# DRV10975_3-ph_Sensorless_BLDC_Motor_Driv.net
KiCad netlist of a schematic drawn in Altium Designer
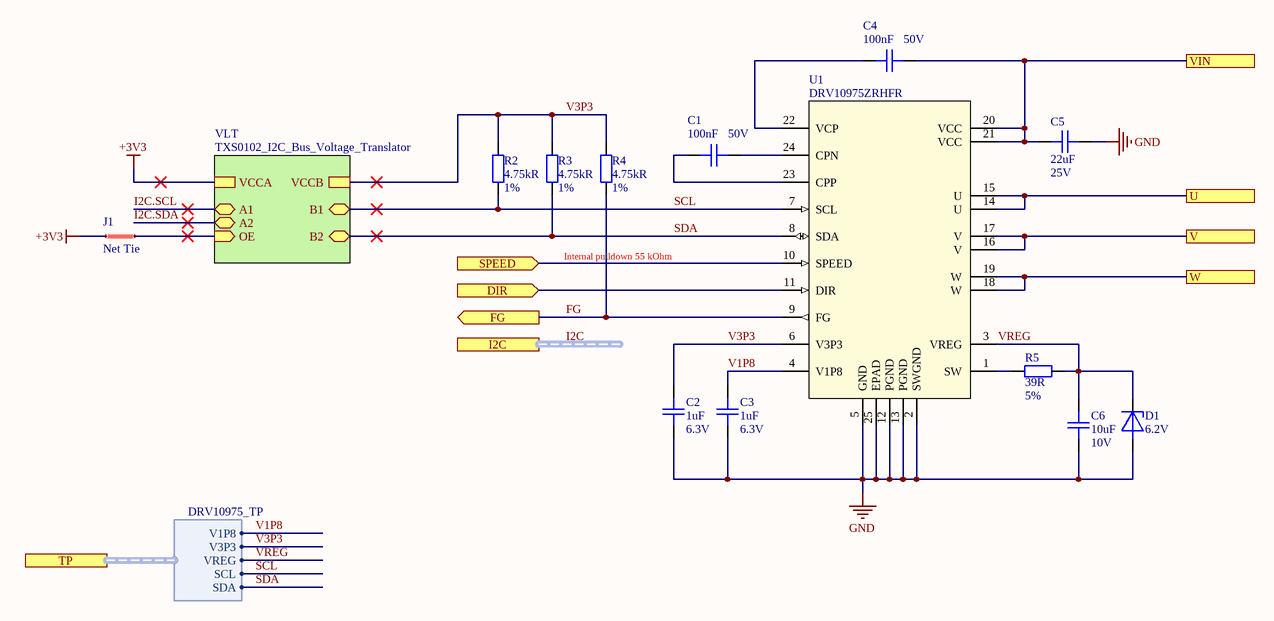
[diagram p0: DRV10975 3-ph Sensorless BLDC Motor Driver.SchDoc]

(export (version "E")
  (design (tool "Eeschema 10.0.6"))
  (components
    (comp (ref "C1")
      (value "CAP CER 0.1UF 50V X7R 0402")
      (footprint "C0402")
      (description "0.1µF ±10% 50V Ceramic Capacitor X7R 0402 (1005 Metric)")
      (fields
        (field (name "MANUFACTURER") "TDK")
        (field (name "MANUFACTURER PART NUMBER") "CGA2B3X7R1H104K050BB")
        (field (name "CAPACITANCE") "100nF")
        (field (name "VOLTAGE") "50V")
      )
      (libsource (lib "capacitors_smd") (part "CAP CER 0.1UF 50V X7R 0402"))
    )
    (comp (ref "C2")
      (value "CAP CER 1UF 6.3V X5R 0402")
      (footprint "C0402")
      (description "1µF ±10% 6.3V Ceramic Capacitor X5R 0402 (1005 Metric)")
      (fields
        (field (name "MANUFACTURER") "Yageo")
        (field (name "MANUFACTURER PART NUMBER") "CC0402KRX5R5BB105")
        (field (name "CAPACITANCE") "1uF")
        (field (name "VOLTAGE RATING") "6.3V")
      )
      (libsource (lib "capacitors_smd") (part "CAP CER 1UF 6.3V X5R 0402"))
    )
    (comp (ref "C3")
      (value "CAP CER 1UF 6.3V X5R 0402")
      (footprint "C0402")
      (description "1µF ±10% 6.3V Ceramic Capacitor X5R 0402 (1005 Metric)")
      (fields
        (field (name "MANUFACTURER") "Yageo")
        (field (name "MANUFACTURER PART NUMBER") "CC0402KRX5R5BB105")
        (field (name "CAPACITANCE") "1uF")
        (field (name "VOLTAGE RATING") "6.3V")
      )
      (libsource (lib "capacitors_smd") (part "CAP CER 1UF 6.3V X5R 0402"))
    )
    (comp (ref "C4")
      (value "CAP CER 0.1UF 50V X7R 0402")
      (footprint "C0402")
      (description "0.1µF ±10% 50V Ceramic Capacitor X7R 0402 (1005 Metric)")
      (fields
        (field (name "MANUFACTURER") "TDK")
        (field (name "MANUFACTURER PART NUMBER") "CGA2B3X7R1H104K050BB")
        (field (name "CAPACITANCE") "100nF")
        (field (name "VOLTAGE") "50V")
      )
      (libsource (lib "capacitors_smd") (part "CAP CER 0.1UF 50V X7R 0402"))
    )
    (comp (ref "C5")
      (value "CAP CER 22UF 25V X5R 0805")
      (footprint "C0805")
      (description "22µF ±20% 25V Ceramic Capacitor X5R 0805 (2012 Metric)")
      (fields
        (field (name "MANUFACTURER") "Yageo")
        (field (name "MANUFACTURER PART NUMBER") "CC0805MKX5R8BB226")
        (field (name "CAPACITANCE") "22uF")
        (field (name "VOLTAGE RATING") "25V")
      )
      (libsource (lib "capacitors_smd") (part "CAP CER 22UF 25V X5R 0805"))
    )
    (comp (ref "C6")
      (value "CAP CER 10uF X7R 10% 0805")
      (footprint "C0805")
      (description "Capacitor,10uF,10V,X7R,10%,0805,Murata")
      (fields
        (field (name "MANUFACTURER") "Murata")
        (field (name "MANUFACTURER PART NUMBER") "GRM21BR71A106KA73L")
        (field (name "CAPACITANCE") "10uF")
        (field (name "VOLTAGE RATING") "10V")
      )
      (libsource (lib "capacitors_smd") (part "CAP CER 10uF X7R 10% 0805"))
    )
    (comp (ref "D1")
      (value "Zener Diode 6.2V 2.5W ±5% Surface Mount SOD-123FL")
      (footprint "SOD-123FL")
      (fields
        (field (name "MANUFACTURER") "ON Semiconductor")
        (field (name "MANUFACTURER PART NUMBER") "1SMF5920BT1G")
        (field (name "TOLERANCE") "5%")
        (field (name "ZENER VOLTAGE") "6.2V")
      )
      (libsource (lib "diodes_zener") (part "DIODE ZENER 6.2V 2.5W SOD123FL"))
    )
    (comp (ref "J1")
      (value "Net Tie")
      (footprint "Net Tie 6x30mil")
      (libsource (lib "BLDC_Motor_Driver") (part "Net Tie Line"))
    )
    (comp (ref "R2")
      (value "DNP*")
      (footprint "R0402")
      (description "4.75 kOhms ±1% 0.063W, 1/16W Chip Resistor 0402 (1005 Metric) Moisture Resistant Thick Film")
      (fields
        (field (name "MANUFACTURER") "Yageo")
        (field (name "MANUFACTURER PART NUMBER") "RC0402FR-074K75P")
        (field (name "RESISTANCE") "4.75kR")
        (field (name "TOLERANCE") "1%")
      )
      (libsource (lib "resistors_smd") (part "RES SMD 4.75K OHM 1% 1/16W 0402"))
    )
    (comp (ref "R3")
      (value "DNP*")
      (footprint "R0402")
      (description "4.75 kOhms ±1% 0.063W, 1/16W Chip Resistor 0402 (1005 Metric) Moisture Resistant Thick Film")
      (fields
        (field (name "MANUFACTURER") "Yageo")
        (field (name "MANUFACTURER PART NUMBER") "RC0402FR-074K75P")
        (field (name "RESISTANCE") "4.75kR")
        (field (name "TOLERANCE") "1%")
      )
      (libsource (lib "resistors_smd") (part "RES SMD 4.75K OHM 1% 1/16W 0402"))
    )
    (comp (ref "R4")
      (value "RES SMD 4.75K OHM 1% 1/16W 0402")
      (footprint "R0402")
      (description "4.75 kOhms ±1% 0.063W, 1/16W Chip Resistor 0402 (1005 Metric) Moisture Resistant Thick Film")
      (fields
        (field (name "MANUFACTURER") "Yageo")
        (field (name "MANUFACTURER PART NUMBER") "RC0402FR-074K75P")
        (field (name "RESISTANCE") "4.75kR")
        (field (name "TOLERANCE") "1%")
      )
      (libsource (lib "resistors_smd") (part "RES SMD 4.75K OHM 1% 1/16W 0402"))
    )
    (comp (ref "R5")
      (value "RES SMD 39 OHM 1% 1/4W 1206")
      (footprint "R1206")
      (description "39 Ohms ±5% 0.25W, 1/4W Chip Resistor 1206 (3216 Metric) Moisture Resistant Thick Film")
      (fields
        (field (name "MANUFACTURER") "Yageo")
        (field (name "MANUFACTURER PART NUMBER") "RC1206JR-0739RL")
        (field (name "RESISTANCE") "39R")
        (field (name "TOLERANCE") "5%")
      )
      (libsource (lib "resistors_smd") (part "RES SMD 39 OHM 1% 1/4W 1206"))
    )
    (comp (ref "U1")
      (value "DRV10975ZRHFR")
      (footprint "RHF24_2P65X3P65")
      (description "Multiphase Motor Driver Power MOSFET Analog, I²C, PWM 24-VQFN (5x4)")
      (fields (field (name "MANUFACTURER") "Texas Instruments"))
      (libsource (lib "BLDC_Moto_Driver") (part "IC DRV10975Z BLDC MOTOR DRIVER VQFN-24"))
    )
  )
  (nets
    (net (code "3") (name "+3V3") (class "Default") (node (ref "J1") (pin "1") (pintype "passive")))
    (net (code "4") (name "/DIR") (class "Default")
      (node (ref "U1") (pin "11") (pinfunction "DIR_11") (pintype "input"))
    )
    (net (code "5") (name "/FG") (class "Default")
      (node (ref "R4") (pin "2") (pinfunction "2_2") (pintype "passive"))
      (node (ref "U1") (pin "9") (pinfunction "FG_9") (pintype "output"))
    )
    (net (code "8") (name "/OE") (class "Default") (node (ref "J1") (pin "2") (pintype "passive")))
    (net (code "9") (name "/SCL") (class "Default")
      (node (ref "R2") (pin "2") (pinfunction "2_2") (pintype "passive"))
      (node (ref "U1") (pin "7") (pinfunction "SCL_7") (pintype "input"))
    )
    (net (code "10") (name "/SDA") (class "Default")
      (node (ref "R3") (pin "2") (pinfunction "2_2") (pintype "passive"))
      (node (ref "U1") (pin "8") (pinfunction "SDA_8") (pintype "bidirectional"))
    )
    (net (code "11") (name "/SPEED") (class "Default")
      (node (ref "U1") (pin "10") (pinfunction "SPEED_10") (pintype "input"))
    )
    (net (code "12") (name "/U") (class "Default")
      (node (ref "U1") (pin "14") (pinfunction "U_14") (pintype "power_in"))
      (node (ref "U1") (pin "15") (pinfunction "U_15") (pintype "power_in"))
    )
    (net (code "13") (name "/V") (class "Default")
      (node (ref "U1") (pin "16") (pinfunction "V_16") (pintype "power_in"))
      (node (ref "U1") (pin "17") (pinfunction "V_17") (pintype "power_in"))
    )
    (net (code "14") (name "/V1P8") (class "Default")
      (node (ref "C3") (pin "2") (pinfunction "2_2") (pintype "passive"))
      (node (ref "U1") (pin "4") (pinfunction "V1P8_4") (pintype "power_in"))
    )
    (net (code "15") (name "/V3P3") (class "Default")
      (node (ref "C2") (pin "2") (pinfunction "2_2") (pintype "passive"))
      (node (ref "R2") (pin "1") (pinfunction "1_1") (pintype "passive"))
      (node (ref "R3") (pin "1") (pinfunction "1_1") (pintype "passive"))
      (node (ref "R4") (pin "1") (pinfunction "1_1") (pintype "passive"))
      (node (ref "U1") (pin "6") (pinfunction "V3P3_6") (pintype "power_in"))
    )
    (net (code "16") (name "/VIN") (class "Default")
      (node (ref "C4") (pin "2") (pinfunction "2_2") (pintype "passive"))
      (node (ref "C5") (pin "1") (pinfunction "1_1") (pintype "passive"))
      (node (ref "U1") (pin "20") (pinfunction "VCC_20") (pintype "power_in"))
      (node (ref "U1") (pin "21") (pinfunction "VCC_21") (pintype "power_in"))
    )
    (net (code "17") (name "/VREG") (class "Default")
      (node (ref "C6") (pin "1") (pinfunction "1_1") (pintype "passive"))
      (node (ref "D1") (pin "1") (pinfunction "K_1") (pintype "passive"))
      (node (ref "R5") (pin "2") (pinfunction "2_2") (pintype "passive"))
      (node (ref "U1") (pin "3") (pinfunction "VREG_3") (pintype "power_in"))
    )
    (net (code "18") (name "/W") (class "Default")
      (node (ref "U1") (pin "18") (pinfunction "W_18") (pintype "power_in"))
      (node (ref "U1") (pin "19") (pinfunction "W_19") (pintype "power_in"))
    )
    (net (code "21") (name "GND") (class "Default")
      (node (ref "C2") (pin "1") (pinfunction "1_1") (pintype "passive"))
      (node (ref "C3") (pin "1") (pinfunction "1_1") (pintype "passive"))
      (node (ref "C5") (pin "2") (pinfunction "2_2") (pintype "passive"))
      (node (ref "C6") (pin "2") (pinfunction "2_2") (pintype "passive"))
      (node (ref "D1") (pin "2") (pinfunction "A_2") (pintype "passive"))
      (node (ref "U1") (pin "12") (pinfunction "PGND_12") (pintype "power_in"))
      (node (ref "U1") (pin "13") (pinfunction "PGND_13") (pintype "power_in"))
      (node (ref "U1") (pin "2") (pinfunction "SWGND_2") (pintype "power_in"))
      (node (ref "U1") (pin "25") (pinfunction "EPAD_25") (pintype "power_in"))
      (node (ref "U1") (pin "5") (pinfunction "GND_5") (pintype "power_in"))
    )
    (net (code "22") (name "Net-(U1-CPN)") (class "Default")
      (node (ref "C1") (pin "2") (pinfunction "2_2") (pintype "passive"))
      (node (ref "U1") (pin "24") (pinfunction "CPN_24") (pintype "power_in"))
    )
    (net (code "23") (name "Net-(U1-CPP)") (class "Default")
      (node (ref "C1") (pin "1") (pinfunction "1_1") (pintype "passive"))
      (node (ref "U1") (pin "23") (pinfunction "CPP_23") (pintype "power_in"))
    )
    (net (code "24") (name "Net-(U1-SW)") (class "Default")
      (node (ref "R5") (pin "1") (pinfunction "1_1") (pintype "passive"))
      (node (ref "U1") (pin "1") (pinfunction "SW_1") (pintype "power_in"))
    )
    (net (code "25") (name "Net-(U1-VCP)") (class "Default")
      (node (ref "C4") (pin "1") (pinfunction "1_1") (pintype "passive"))
      (node (ref "U1") (pin "22") (pinfunction "VCP_22") (pintype "power_in"))
    )
  )
)
